# SENSOR.net
KiCad netlist of a schematic drawn in Altium Designer
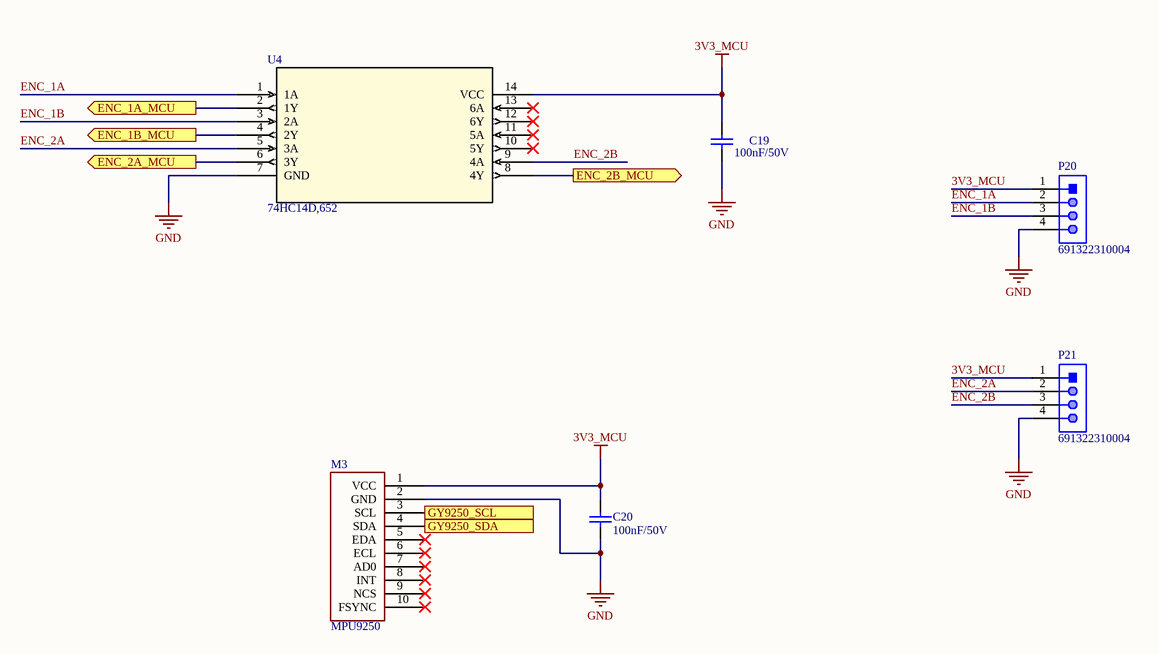
[diagram p0: SENSOR.SchDoc]

(export (version "E")
  (design (tool "Eeschema 10.0.6"))
  (components
    (comp (ref "C19")
      (value "100nF/50V")
      (footprint "CAP-SM-0805")
      (description "CAP CER 1000PF 100V X7R 0805")
      (fields
        (field (name "MANUFACTURER") "Johanson Dielectrics Inc.")
        (field (name "MANUFACTURER PART NUMBER") "101X15W102MV4E")
      )
      (libsource (lib "PIF_ROBOT") (part "Cap-1nF-50V-0805"))
    )
    (comp (ref "C20")
      (value "100nF/50V")
      (footprint "CAP-SM-0805")
      (description "CAP CER 1000PF 100V X7R 0805")
      (fields
        (field (name "MANUFACTURER") "Johanson Dielectrics Inc.")
        (field (name "MANUFACTURER PART NUMBER") "101X15W102MV4E")
      )
      (libsource (lib "PIF_ROBOT") (part "Cap-1nF-50V-0805"))
    )
    (comp (ref "M3") (value "MPU9250") (footprint "MPU9250") (libsource (lib "PIF_ROBOT") (part "MPU9250")))
    (comp (ref "P20")
      (value "691322310004")
      (footprint "691322310004")
      (description "WR-TBL Serie 322 Horizontal PCB Header, Pluggable, pitch 3.81mm, 4p")
      (fields (field (name "PUBLISHER") "Wurth Elektronik"))
      (libsource (lib "PIF_ROBOT") (part "691322310004"))
    )
    (comp (ref "P21")
      (value "691322310004")
      (footprint "691322310004")
      (description "WR-TBL Serie 322 Horizontal PCB Header, Pluggable, pitch 3.81mm, 4p")
      (fields (field (name "PUBLISHER") "Wurth Elektronik"))
      (libsource (lib "PIF_ROBOT") (part "691322310004"))
    )
    (comp (ref "U4")
      (value "74HC14D,652")
      (footprint "74hc14d")
      (description "No Description Available")
      (fields (field (name "COPYRIGHT") "Copyright (C) 2016 Accelerated Designs. All rights reserved"))
      (libsource (lib "PIF_ROBOT") (part "74HC14D,652"))
    )
  )
  (nets
    (net (code "1") (name "/ENC_1A") (class "Default")
      (node (ref "P20") (pin "2") (pinfunction "2_2") (pintype "passive"))
      (node (ref "U4") (pin "1") (pinfunction "1A_1") (pintype "input"))
    )
    (net (code "2") (name "/ENC_1A_MCU") (class "Default")
      (node (ref "U4") (pin "2") (pinfunction "1Y_2") (pintype "output"))
    )
    (net (code "3") (name "/ENC_1B") (class "Default")
      (node (ref "P20") (pin "3") (pinfunction "3_3") (pintype "passive"))
      (node (ref "U4") (pin "3") (pinfunction "2A_3") (pintype "input"))
    )
    (net (code "4") (name "/ENC_1B_MCU") (class "Default")
      (node (ref "U4") (pin "4") (pinfunction "2Y_4") (pintype "output"))
    )
    (net (code "5") (name "/ENC_2A") (class "Default")
      (node (ref "P21") (pin "2") (pinfunction "2_2") (pintype "passive"))
      (node (ref "U4") (pin "5") (pinfunction "3A_5") (pintype "input"))
    )
    (net (code "6") (name "/ENC_2A_MCU") (class "Default")
      (node (ref "U4") (pin "6") (pinfunction "3Y_6") (pintype "output"))
    )
    (net (code "7") (name "/ENC_2B") (class "Default")
      (node (ref "P21") (pin "3") (pinfunction "3_3") (pintype "passive"))
      (node (ref "U4") (pin "9") (pinfunction "4A_9") (pintype "input"))
    )
    (net (code "8") (name "/ENC_2B_MCU") (class "Default")
      (node (ref "U4") (pin "8") (pinfunction "4Y_8") (pintype "output"))
    )
    (net (code "9") (name "/GY9250_SCL") (class "Default")
      (node (ref "M3") (pin "3") (pinfunction "SCL_3") (pintype "passive"))
    )
    (net (code "10") (name "/GY9250_SDA") (class "Default")
      (node (ref "M3") (pin "4") (pinfunction "SDA_4") (pintype "passive"))
    )
    (net (code "11") (name "3V3_MCU") (class "Default")
      (node (ref "C19") (pin "2") (pinfunction "2_2") (pintype "passive"))
      (node (ref "C20") (pin "2") (pinfunction "2_2") (pintype "passive"))
      (node (ref "M3") (pin "1") (pinfunction "VCC_1") (pintype "passive"))
      (node (ref "P20") (pin "1") (pinfunction "1_1") (pintype "passive"))
      (node (ref "P21") (pin "1") (pinfunction "1_1") (pintype "passive"))
      (node (ref "U4") (pin "14") (pinfunction "VCC_14") (pintype "power_in"))
    )
    (net (code "12") (name "GND") (class "Default")
      (node (ref "C19") (pin "1") (pinfunction "1_1") (pintype "passive"))
      (node (ref "C20") (pin "1") (pinfunction "1_1") (pintype "passive"))
      (node (ref "M3") (pin "2") (pinfunction "GND_2") (pintype "passive"))
      (node (ref "P20") (pin "4") (pinfunction "4_4") (pintype "passive"))
      (node (ref "P21") (pin "4") (pinfunction "4_4") (pintype "passive"))
      (node (ref "U4") (pin "7") (pinfunction "GND_7") (pintype "power_in"))
    )
    (net (code "13") (name "unconnected-(M3-AD0-Pad7)") (class "Default")
      (node (ref "M3") (pin "7") (pinfunction "AD0_7") (pintype "passive+no_connect"))
    )
    (net (code "14") (name "unconnected-(M3-ECL-Pad6)") (class "Default")
      (node (ref "M3") (pin "6") (pinfunction "ECL_6") (pintype "passive+no_connect"))
    )
    (net (code "15") (name "unconnected-(M3-EDA-Pad5)") (class "Default")
      (node (ref "M3") (pin "5") (pinfunction "EDA_5") (pintype "passive+no_connect"))
    )
    (net (code "16") (name "unconnected-(M3-FSYNC-Pad10)") (class "Default")
      (node (ref "M3") (pin "10") (pinfunction "FSYNC_10") (pintype "passive+no_connect"))
    )
    (net (code "17") (name "unconnected-(M3-INT-Pad8)") (class "Default")
      (node (ref "M3") (pin "8") (pinfunction "INT_8") (pintype "passive+no_connect"))
    )
    (net (code "18") (name "unconnected-(M3-NCS-Pad9)") (class "Default")
      (node (ref "M3") (pin "9") (pinfunction "NCS_9") (pintype "passive+no_connect"))
    )
    (net (code "19") (name "unconnected-(U4-5A-Pad11)") (class "Default")
      (node (ref "U4") (pin "11") (pinfunction "5A_11") (pintype "input+no_connect"))
    )
    (net (code "20") (name "unconnected-(U4-5Y-Pad10)") (class "Default")
      (node (ref "U4") (pin "10") (pinfunction "5Y_10") (pintype "output+no_connect"))
    )
    (net (code "21") (name "unconnected-(U4-6A-Pad13)") (class "Default")
      (node (ref "U4") (pin "13") (pinfunction "6A_13") (pintype "input+no_connect"))
    )
    (net (code "22") (name "unconnected-(U4-6Y-Pad12)") (class "Default")
      (node (ref "U4") (pin "12") (pinfunction "6Y_12") (pintype "output+no_connect"))
    )
  )
)
